# Generator28.net
KiCad netlist of a schematic drawn in Altium Designer
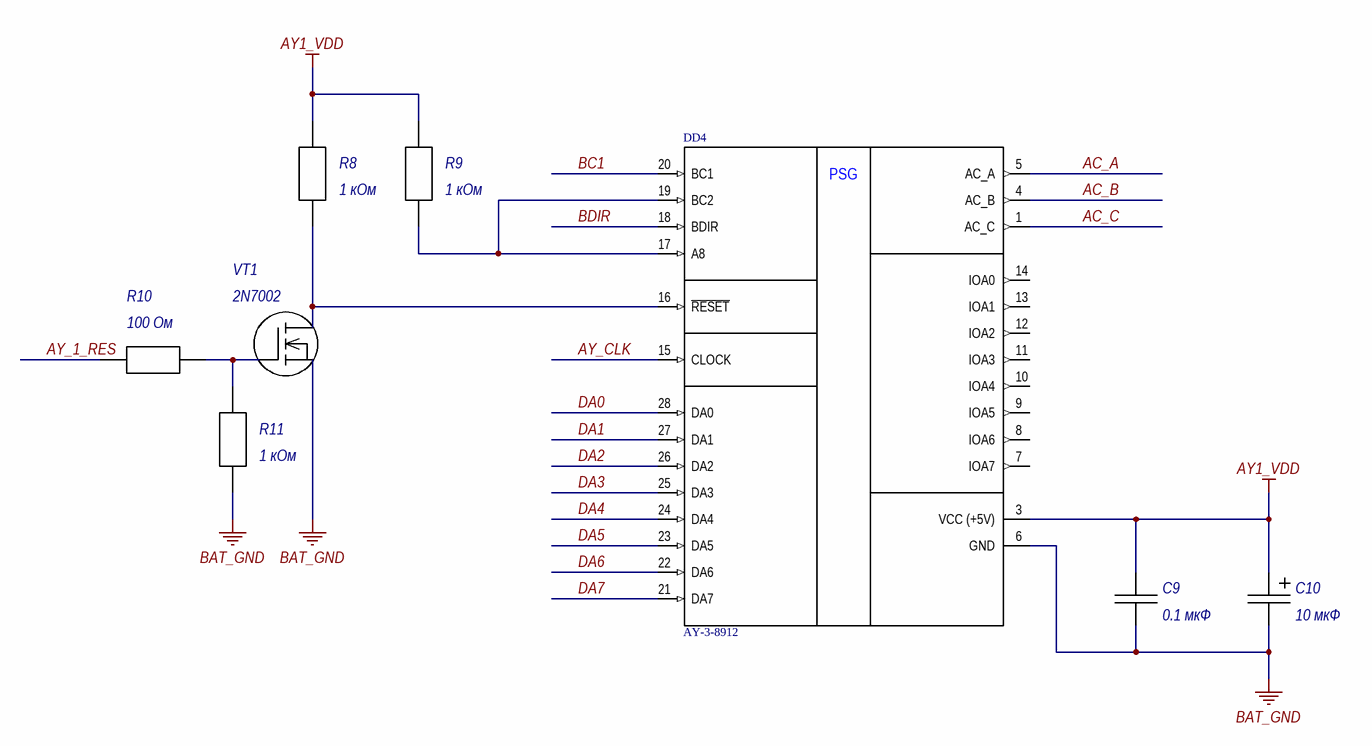
[diagram p0: Generator28.SchDoc]

(export (version "E")
  (design (tool "Eeschema 10.0.6"))
  (components
    (comp (ref "C9")
      (value "0.1 мкФ")
      (footprint "C 1206")
      (description "SMD Capacitor 1206")
      (fields
        (field (name "TOLERANCE") "/Укажите допуск в процентах/")
        (field (name "MANUFACTURER") "/Укажите компанию-производителя/")
      )
      (libsource (lib "my_lib") (part "CAP 1206"))
    )
    (comp (ref "C10")
      (value "10 мкФ")
      (footprint "C TAN_A")
      (description "SMD Tantalium Capacitor A")
      (libsource (lib "my_lib") (part "CAP TAN_A"))
    )
    (comp (ref "DD4")
      (value "AY-3-8912")
      (footprint "DIP28_PLUS_MCU")
      (libsource (lib "my_lib") (part "AY-3-8912"))
    )
    (comp (ref "R8") (value "1 кОм") (footprint "RES 0805") (libsource (lib "my_lib") (part "RES 0805")))
    (comp (ref "R9") (value "1 кОм") (footprint "RES 0805") (libsource (lib "my_lib") (part "RES 0805")))
    (comp (ref "R10") (value "100 Ом") (footprint "RES 0805") (libsource (lib "my_lib") (part "RES 0805")))
    (comp (ref "R11") (value "1 кОм") (footprint "RES 0805") (libsource (lib "my_lib") (part "RES 0805")))
    (comp (ref "VT1")
      (value "2N7002")
      (footprint "SOT-23")
      (description "60 V, 300 mA N-channel Trench MOSFET")
      (fields (field (name "MANUFACTURER") "NXP"))
      (libsource (lib "my_lib") (part "2N7002"))
    )
  )
  (nets
    (net (code "1") (name "/AC_A") (class "Default")
      (node (ref "DD4") (pin "5") (pinfunction "AC_A_5") (pintype "output"))
    )
    (net (code "2") (name "/AC_B") (class "Default")
      (node (ref "DD4") (pin "4") (pinfunction "AC_B_4") (pintype "output"))
    )
    (net (code "3") (name "/AC_C") (class "Default")
      (node (ref "DD4") (pin "1") (pinfunction "AC_C_1") (pintype "output"))
    )
    (net (code "4") (name "/AY_1_RES") (class "Default")
      (node (ref "R10") (pin "1") (pinfunction "1_1") (pintype "passive"))
    )
    (net (code "5") (name "/AY_CLK") (class "Default")
      (node (ref "DD4") (pin "15") (pinfunction "CLOCK_15") (pintype "input"))
    )
    (net (code "6") (name "/BC1") (class "Default")
      (node (ref "DD4") (pin "20") (pinfunction "BC1_20") (pintype "input"))
    )
    (net (code "7") (name "/BDIR") (class "Default")
      (node (ref "DD4") (pin "18") (pinfunction "BDIR_18") (pintype "input"))
    )
    (net (code "8") (name "/DA0") (class "Default")
      (node (ref "DD4") (pin "28") (pinfunction "DA0_28") (pintype "input"))
    )
    (net (code "9") (name "/DA1") (class "Default")
      (node (ref "DD4") (pin "27") (pinfunction "DA1_27") (pintype "input"))
    )
    (net (code "10") (name "/DA2") (class "Default")
      (node (ref "DD4") (pin "26") (pinfunction "DA2_26") (pintype "input"))
    )
    (net (code "11") (name "/DA3") (class "Default")
      (node (ref "DD4") (pin "25") (pinfunction "DA3_25") (pintype "input"))
    )
    (net (code "12") (name "/DA4") (class "Default")
      (node (ref "DD4") (pin "24") (pinfunction "DA4_24") (pintype "input"))
    )
    (net (code "13") (name "/DA5") (class "Default")
      (node (ref "DD4") (pin "23") (pinfunction "DA5_23") (pintype "input"))
    )
    (net (code "14") (name "/DA6") (class "Default")
      (node (ref "DD4") (pin "22") (pinfunction "DA6_22") (pintype "input"))
    )
    (net (code "15") (name "/DA7") (class "Default")
      (node (ref "DD4") (pin "21") (pinfunction "DA7_21") (pintype "input"))
    )
    (net (code "16") (name "AY1_VDD") (class "Default")
      (node (ref "C10") (pin "1") (pinfunction "1_1") (pintype "passive"))
      (node (ref "C9") (pin "1") (pinfunction "1_1") (pintype "passive"))
      (node (ref "DD4") (pin "3") (pinfunction "VCC_(+5V)_3") (pintype "power_in"))
      (node (ref "R8") (pin "2") (pinfunction "2_2") (pintype "passive"))
      (node (ref "R9") (pin "1") (pinfunction "1_1") (pintype "passive"))
    )
    (net (code "17") (name "BAT_GND") (class "Default")
      (node (ref "C10") (pin "2") (pinfunction "2_2") (pintype "passive"))
      (node (ref "C9") (pin "2") (pinfunction "2_2") (pintype "passive"))
      (node (ref "DD4") (pin "6") (pinfunction "GND_6") (pintype "power_in"))
      (node (ref "R11") (pin "1") (pinfunction "1_1") (pintype "passive"))
      (node (ref "VT1") (pin "2") (pinfunction "S_2") (pintype "passive"))
    )
    (net (code "18") (name "Net-(DD4-A8)") (class "Default")
      (node (ref "DD4") (pin "17") (pinfunction "A8_17") (pintype "input"))
      (node (ref "DD4") (pin "19") (pinfunction "BC2_19") (pintype "input"))
      (node (ref "R9") (pin "2") (pinfunction "2_2") (pintype "passive"))
    )
    (net (code "19") (name "Net-(DD4-~{RESET})") (class "Default")
      (node (ref "DD4") (pin "16") (pinfunction "~{RESET}_16") (pintype "input"))
      (node (ref "R8") (pin "1") (pinfunction "1_1") (pintype "passive"))
      (node (ref "VT1") (pin "3") (pinfunction "D_3") (pintype "passive"))
    )
    (net (code "20") (name "Net-(VT1-G)") (class "Default")
      (node (ref "R10") (pin "2") (pinfunction "2_2") (pintype "passive"))
      (node (ref "R11") (pin "2") (pinfunction "2_2") (pintype "passive"))
      (node (ref "VT1") (pin "1") (pinfunction "G_1") (pintype "passive"))
    )
    (net (code "21") (name "unconnected-(DD4-IOA0-Pad14)") (class "Default")
      (node (ref "DD4") (pin "14") (pinfunction "IOA0_14") (pintype "output"))
    )
    (net (code "22") (name "unconnected-(DD4-IOA1-Pad13)") (class "Default")
      (node (ref "DD4") (pin "13") (pinfunction "IOA1_13") (pintype "output"))
    )
    (net (code "23") (name "unconnected-(DD4-IOA2-Pad12)") (class "Default")
      (node (ref "DD4") (pin "12") (pinfunction "IOA2_12") (pintype "output"))
    )
    (net (code "24") (name "unconnected-(DD4-IOA3-Pad11)") (class "Default")
      (node (ref "DD4") (pin "11") (pinfunction "IOA3_11") (pintype "output"))
    )
    (net (code "25") (name "unconnected-(DD4-IOA4-Pad10)") (class "Default")
      (node (ref "DD4") (pin "10") (pinfunction "IOA4_10") (pintype "output"))
    )
    (net (code "26") (name "unconnected-(DD4-IOA5-Pad9)") (class "Default")
      (node (ref "DD4") (pin "9") (pinfunction "IOA5_9") (pintype "output"))
    )
    (net (code "27") (name "unconnected-(DD4-IOA6-Pad8)") (class "Default")
      (node (ref "DD4") (pin "8") (pinfunction "IOA6_8") (pintype "output"))
    )
    (net (code "28") (name "unconnected-(DD4-IOA7-Pad7)") (class "Default")
      (node (ref "DD4") (pin "7") (pinfunction "IOA7_7") (pintype "output"))
    )
  )
)
